# IMX7S_PMIC.net
KiCad netlist of a schematic drawn in Altium Designer
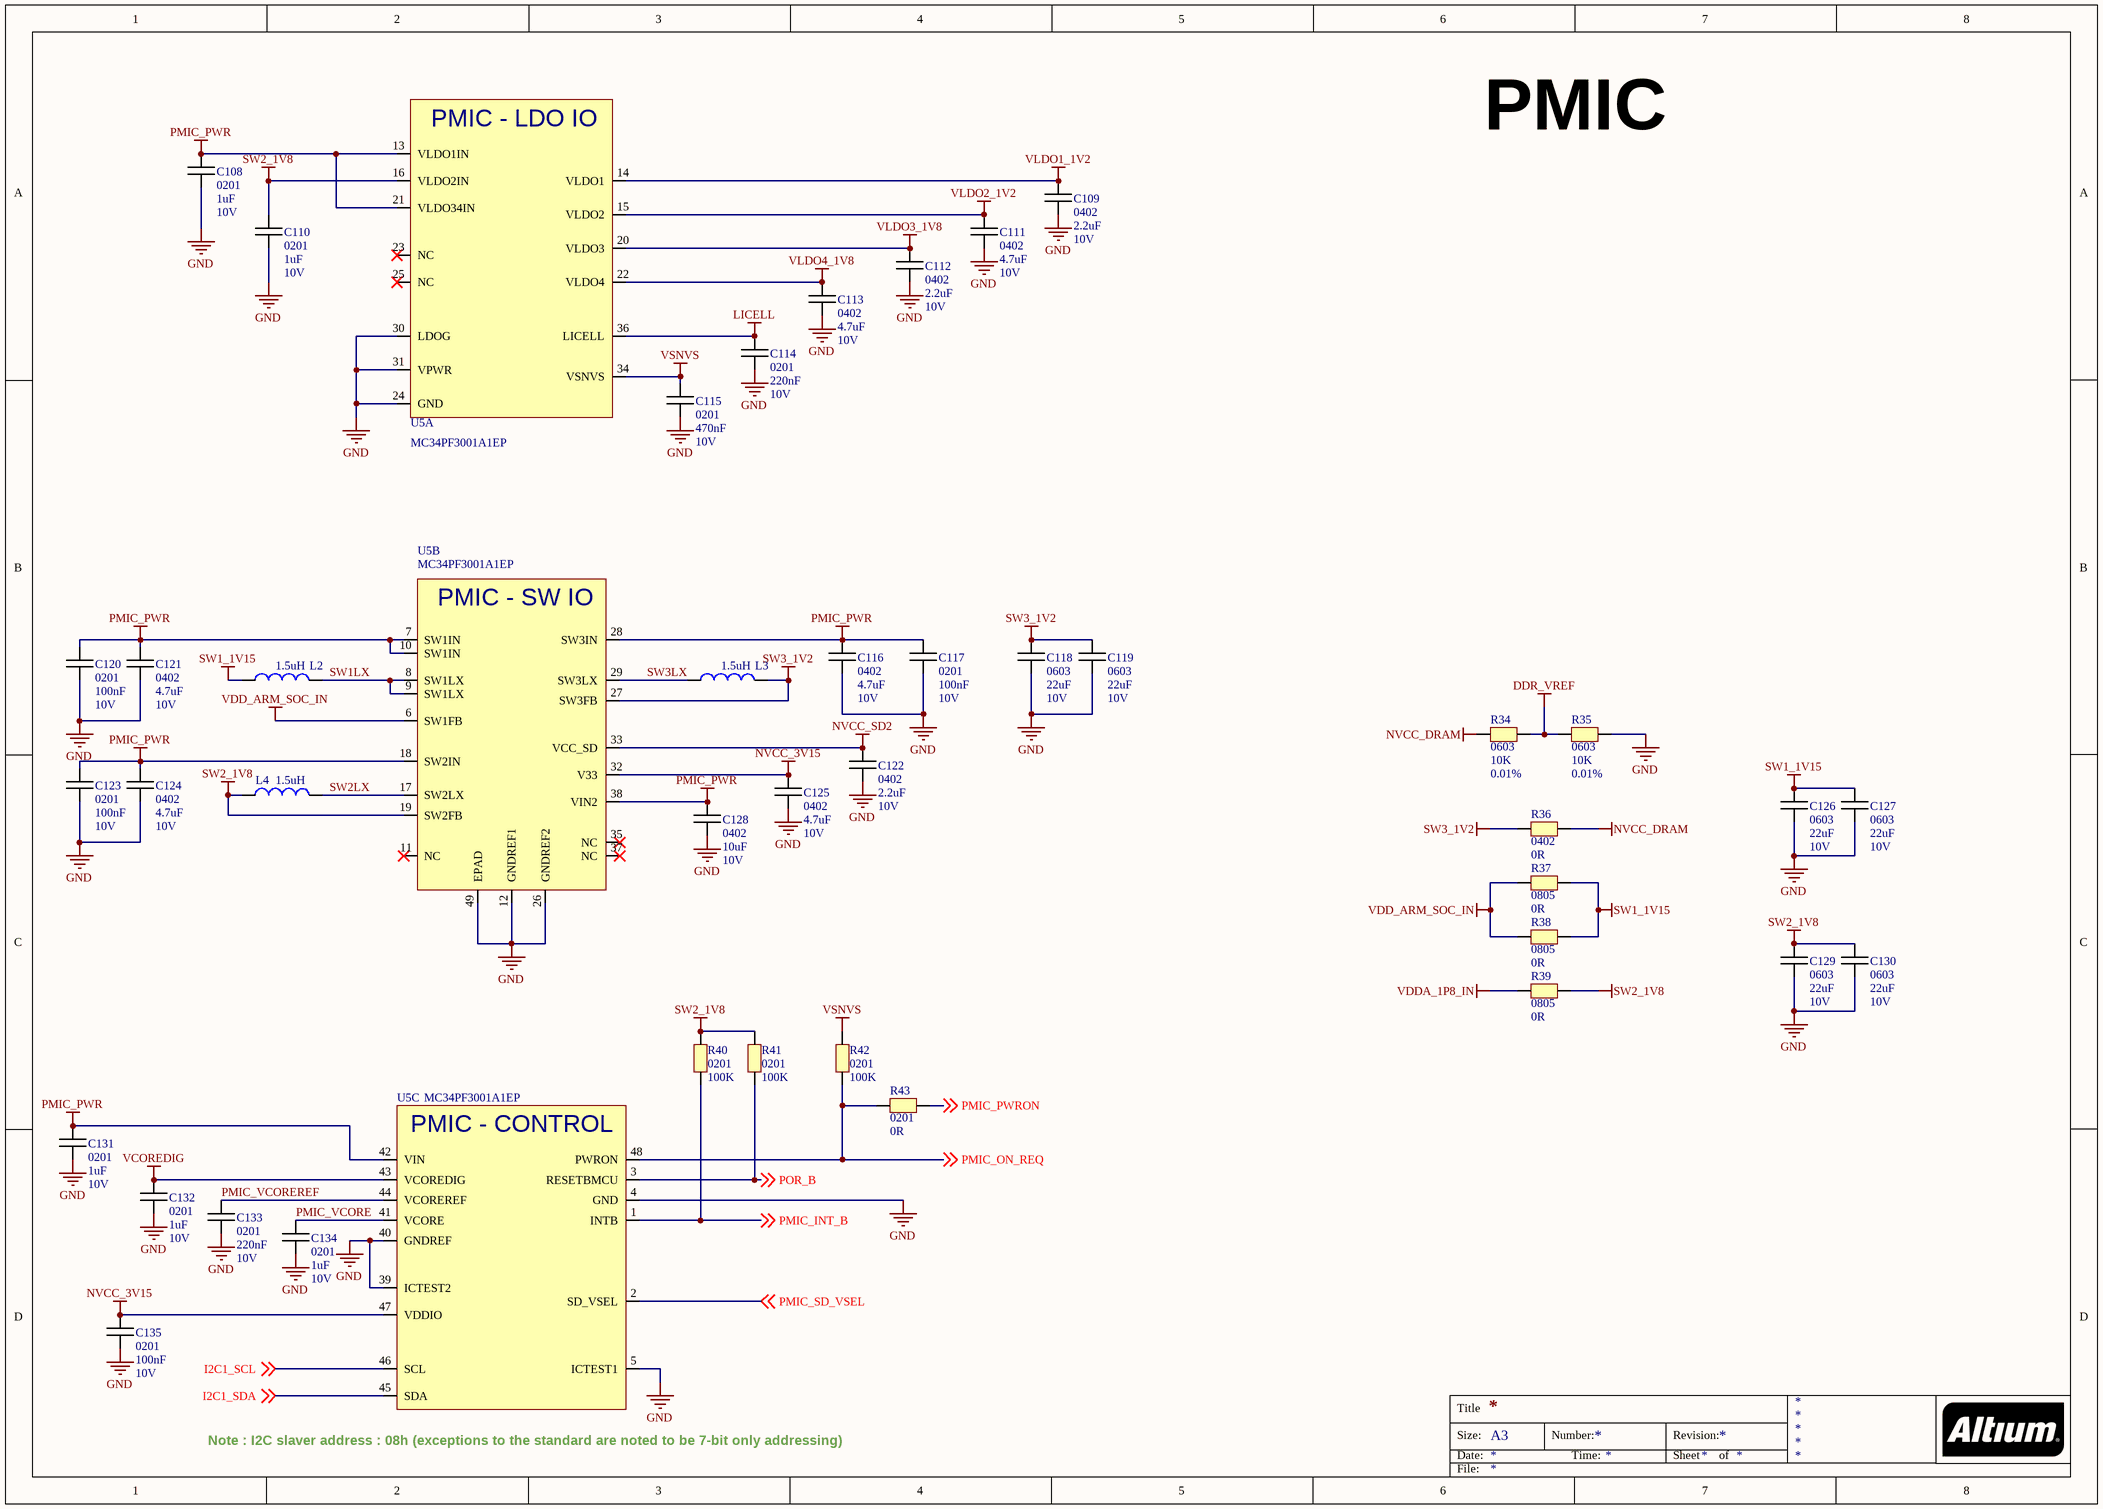
[diagram p0: IMX7S_PMIC.SchDoc]

(export (version "E")
  (design (tool "Eeschema 10.0.6"))
  (components
    (comp (ref "C108")
      (value "1uF")
      (footprint "C0201")
      (description "CAP CER 1UF 6.3V X5R 0201")
      (fields
        (field (name "PACKAGE") "0201")
        (field (name "VOLTAGE") "10V")
        (field (name "TOLERANCE") "20%")
        (field (name "Comment") "C0201")
      )
      (libsource (lib "Schlib_IMX7") (part "C0201"))
    )
    (comp (ref "C109")
      (value "2.2uF")
      (footprint "C0402")
      (fields
        (field (name "PACKAGE") "0402")
        (field (name "VOLTAGE") "10V")
        (field (name "TOLERANCE") "20%")
        (field (name "Comment") "C0402")
      )
      (libsource (lib "Schlib_IMX7") (part "C0402"))
    )
    (comp (ref "C110")
      (value "1uF")
      (footprint "C0201")
      (description "CAP CER 1UF 6.3V X5R 0201")
      (fields
        (field (name "PACKAGE") "0201")
        (field (name "VOLTAGE") "10V")
        (field (name "TOLERANCE") "20%")
        (field (name "Comment") "C0201")
      )
      (libsource (lib "Schlib_IMX7") (part "C0201"))
    )
    (comp (ref "C111")
      (value "4.7uF")
      (footprint "C0402")
      (fields (field (name "PACKAGE") "0402") (field (name "VOLTAGE") "10V") (field (name "Comment") "C0402"))
      (libsource (lib "Schlib_IMX7") (part "C0402"))
    )
    (comp (ref "C112")
      (value "2.2uF")
      (footprint "C0402")
      (fields
        (field (name "PACKAGE") "0402")
        (field (name "VOLTAGE") "10V")
        (field (name "TOLERANCE") "20%")
        (field (name "Comment") "C0402")
      )
      (libsource (lib "Schlib_IMX7") (part "C0402"))
    )
    (comp (ref "C113")
      (value "4.7uF")
      (footprint "C0402")
      (fields (field (name "PACKAGE") "0402") (field (name "VOLTAGE") "10V") (field (name "Comment") "C0402"))
      (libsource (lib "Schlib_IMX7") (part "C0402"))
    )
    (comp (ref "C114")
      (value "220nF")
      (footprint "C0201")
      (fields
        (field (name "PACKAGE") "0201")
        (field (name "VOLTAGE") "10V")
        (field (name "TOLERANCE") "10%")
        (field (name "Comment") "C0201")
      )
      (libsource (lib "Schlib_IMX7") (part "C0201"))
    )
    (comp (ref "C115")
      (value "470nF")
      (footprint "C0201")
      (fields (field (name "PACKAGE") "0201") (field (name "VOLTAGE") "10V") (field (name "Comment") "C0201"))
      (libsource (lib "Schlib_IMX7") (part "C0201"))
    )
    (comp (ref "C116")
      (value "4.7uF")
      (footprint "C0402")
      (fields (field (name "PACKAGE") "0402") (field (name "VOLTAGE") "10V") (field (name "Comment") "C0402"))
      (libsource (lib "Schlib_IMX7") (part "C0402"))
    )
    (comp (ref "C117")
      (value "100nF")
      (footprint "C0201")
      (fields
        (field (name "PACKAGE") "0201")
        (field (name "VOLTAGE") "10V")
        (field (name "TOLERANCE") "10%")
        (field (name "Comment") "C0201")
      )
      (libsource (lib "Schlib_IMX7") (part "C0201"))
    )
    (comp (ref "C118")
      (value "22uF")
      (footprint "C0603")
      (description "CAP, MLCC, X5R, 22UF, 10V, 0603")
      (fields
        (field (name "PACKAGE") "0603")
        (field (name "VOLTAGE") "10V")
        (field (name "TOLERANCE") "20%")
        (field (name "Comment") "C0603")
      )
      (libsource (lib "Schlib_IMX7") (part "C0603"))
    )
    (comp (ref "C119")
      (value "22uF")
      (footprint "C0603")
      (description "CAP, MLCC, X5R, 22UF, 10V, 0603")
      (fields
        (field (name "PACKAGE") "0603")
        (field (name "VOLTAGE") "10V")
        (field (name "TOLERANCE") "20%")
        (field (name "Comment") "C0603")
      )
      (libsource (lib "Schlib_IMX7") (part "C0603"))
    )
    (comp (ref "C120")
      (value "100nF")
      (footprint "C0201")
      (fields
        (field (name "PACKAGE") "0201")
        (field (name "VOLTAGE") "10V")
        (field (name "TOLERANCE") "10%")
        (field (name "Comment") "C0201")
      )
      (libsource (lib "Schlib_IMX7") (part "C0201"))
    )
    (comp (ref "C121")
      (value "4.7uF")
      (footprint "C0402")
      (fields (field (name "PACKAGE") "0402") (field (name "VOLTAGE") "10V") (field (name "Comment") "C0402"))
      (libsource (lib "Schlib_IMX7") (part "C0402"))
    )
    (comp (ref "C122")
      (value "2.2uF")
      (footprint "C0402")
      (fields
        (field (name "PACKAGE") "0402")
        (field (name "VOLTAGE") "10V")
        (field (name "TOLERANCE") "20%")
        (field (name "Comment") "C0402")
      )
      (libsource (lib "Schlib_IMX7") (part "C0402"))
    )
    (comp (ref "C123")
      (value "100nF")
      (footprint "C0201")
      (fields
        (field (name "PACKAGE") "0201")
        (field (name "VOLTAGE") "10V")
        (field (name "TOLERANCE") "10%")
        (field (name "Comment") "C0201")
      )
      (libsource (lib "Schlib_IMX7") (part "C0201"))
    )
    (comp (ref "C124")
      (value "4.7uF")
      (footprint "C0402")
      (fields (field (name "PACKAGE") "0402") (field (name "VOLTAGE") "10V") (field (name "Comment") "C0402"))
      (libsource (lib "Schlib_IMX7") (part "C0402"))
    )
    (comp (ref "C125")
      (value "4.7uF")
      (footprint "C0402")
      (fields (field (name "PACKAGE") "0402") (field (name "VOLTAGE") "10V") (field (name "Comment") "C0402"))
      (libsource (lib "Schlib_IMX7") (part "C0402"))
    )
    (comp (ref "C126")
      (value "22uF")
      (footprint "C0603")
      (description "CAP, MLCC, X5R, 22UF, 10V, 0603")
      (fields
        (field (name "PACKAGE") "0603")
        (field (name "VOLTAGE") "10V")
        (field (name "TOLERANCE") "20%")
        (field (name "Comment") "C0603")
      )
      (libsource (lib "Schlib_IMX7") (part "C0603"))
    )
    (comp (ref "C127")
      (value "22uF")
      (footprint "C0603")
      (description "CAP, MLCC, X5R, 22UF, 10V, 0603")
      (fields
        (field (name "PACKAGE") "0603")
        (field (name "VOLTAGE") "10V")
        (field (name "TOLERANCE") "20%")
        (field (name "Comment") "C0603")
      )
      (libsource (lib "Schlib_IMX7") (part "C0603"))
    )
    (comp (ref "C128")
      (value "10uF")
      (footprint "C0402")
      (fields
        (field (name "PACKAGE") "0402")
        (field (name "VOLTAGE") "10V")
        (field (name "TOLERANCE") "20%")
        (field (name "Comment") "C0402")
      )
      (libsource (lib "Schlib_IMX7") (part "C0402"))
    )
    (comp (ref "C129")
      (value "22uF")
      (footprint "C0603")
      (description "CAP, MLCC, X5R, 22UF, 10V, 0603")
      (fields
        (field (name "PACKAGE") "0603")
        (field (name "VOLTAGE") "10V")
        (field (name "TOLERANCE") "20%")
        (field (name "Comment") "C0603")
      )
      (libsource (lib "Schlib_IMX7") (part "C0603"))
    )
    (comp (ref "C130")
      (value "22uF")
      (footprint "C0603")
      (description "CAP, MLCC, X5R, 22UF, 10V, 0603")
      (fields
        (field (name "PACKAGE") "0603")
        (field (name "VOLTAGE") "10V")
        (field (name "TOLERANCE") "20%")
        (field (name "Comment") "C0603")
      )
      (libsource (lib "Schlib_IMX7") (part "C0603"))
    )
    (comp (ref "C131")
      (value "1uF")
      (footprint "C0201")
      (description "CAP CER 1UF 6.3V X5R 0201")
      (fields
        (field (name "PACKAGE") "0201")
        (field (name "VOLTAGE") "10V")
        (field (name "TOLERANCE") "20%")
        (field (name "Comment") "C0201")
      )
      (libsource (lib "Schlib_IMX7") (part "C0201"))
    )
    (comp (ref "C132")
      (value "1uF")
      (footprint "C0201")
      (description "CAP CER 1UF 6.3V X5R 0201")
      (fields
        (field (name "PACKAGE") "0201")
        (field (name "VOLTAGE") "10V")
        (field (name "TOLERANCE") "20%")
        (field (name "Comment") "C0201")
      )
      (libsource (lib "Schlib_IMX7") (part "C0201"))
    )
    (comp (ref "C133")
      (value "220nF")
      (footprint "C0201")
      (fields
        (field (name "PACKAGE") "0201")
        (field (name "VOLTAGE") "10V")
        (field (name "TOLERANCE") "10%")
        (field (name "Comment") "C0201")
      )
      (libsource (lib "Schlib_IMX7") (part "C0201"))
    )
    (comp (ref "C134")
      (value "1uF")
      (footprint "C0201")
      (description "CAP CER 1UF 6.3V X5R 0201")
      (fields
        (field (name "PACKAGE") "0201")
        (field (name "VOLTAGE") "10V")
        (field (name "TOLERANCE") "20%")
        (field (name "Comment") "C0201")
      )
      (libsource (lib "Schlib_IMX7") (part "C0201"))
    )
    (comp (ref "C135")
      (value "100nF")
      (footprint "C0201")
      (fields
        (field (name "PACKAGE") "0201")
        (field (name "VOLTAGE") "10V")
        (field (name "TOLERANCE") "10%")
        (field (name "Comment") "C0201")
      )
      (libsource (lib "Schlib_IMX7") (part "C0201"))
    )
    (comp (ref "L2")
      (value "1.5uH")
      (footprint "SELF")
      (fields (field (name "Comment") "Self"))
      (libsource (lib "Schlib_IMX7") (part "Self"))
    )
    (comp (ref "L3")
      (value "1.5uH")
      (footprint "SELF")
      (fields (field (name "Comment") "Self"))
      (libsource (lib "Schlib_IMX7") (part "Self"))
    )
    (comp (ref "L4")
      (value "1.5uH")
      (footprint "SELF")
      (fields (field (name "Comment") "Self"))
      (libsource (lib "Schlib_IMX7") (part "Self"))
    )
    (comp (ref "R34")
      (value "10K")
      (footprint "R0603")
      (description "GLOVE, NITROTOUGH, M, N230 - More Details")
      (fields
        (field (name "PACKAGE") "0603")
        (field (name "VOLTAGE") "0.01%")
        (field (name "TOLERANCE") "0.01%")
        (field (name "Comment") "R0603")
      )
      (libsource (lib "Schlib_IMX7") (part "R0603"))
    )
    (comp (ref "R35")
      (value "10K")
      (footprint "R0603")
      (description "GLOVE, NITROTOUGH, M, N230 - More Details")
      (fields
        (field (name "PACKAGE") "0603")
        (field (name "VOLTAGE") "0.01%")
        (field (name "TOLERANCE") "0.01%")
        (field (name "Comment") "R0603")
      )
      (libsource (lib "Schlib_IMX7") (part "R0603"))
    )
    (comp (ref "R36")
      (value "0R")
      (footprint "R0402")
      (description "MULTICOMP - MCSR04X000 PTL - RES, 0R0, 0.0625W, 0402, CERAMIC")
      (fields (field (name "PACKAGE") "0402") (field (name "VOLTAGE") "0V") (field (name "Comment") "R0402"))
      (libsource (lib "Schlib_IMX7") (part "R0402"))
    )
    (comp (ref "R37")
      (value "0R")
      (footprint "R0805")
      (description "MULTICOMP - MC01W08050R - RES, 0R0, 0.1W, , THICK FILM")
      (fields (field (name "PACKAGE") "0805") (field (name "VOLTAGE") "0V") (field (name "Comment") "R0805"))
      (libsource (lib "Schlib_IMX7") (part "R0805"))
    )
    (comp (ref "R38")
      (value "0R")
      (footprint "R0805")
      (description "MULTICOMP - MC01W08050R - RES, 0R0, 0.1W, , THICK FILM")
      (fields (field (name "PACKAGE") "0805") (field (name "VOLTAGE") "0V") (field (name "Comment") "R0805"))
      (libsource (lib "Schlib_IMX7") (part "R0805"))
    )
    (comp (ref "R39")
      (value "0R")
      (footprint "R0805")
      (description "MULTICOMP - MC01W08050R - RES, 0R0, 0.1W, , THICK FILM")
      (fields (field (name "PACKAGE") "0805") (field (name "VOLTAGE") "0V") (field (name "Comment") "R0805"))
      (libsource (lib "Schlib_IMX7") (part "R0805"))
    )
    (comp (ref "R40")
      (value "100K")
      (footprint "R0201")
      (description "MULTICOMP - MCWR02X1003FAL - RES, 100K, 1%, 0.05W, THICK FILM")
      (fields (field (name "PACKAGE") "0201") (field (name "VOLTAGE") "0V") (field (name "TOLERANCE") "1%"))
      (libsource (lib "Schlib_IMX7") (part "R0201"))
    )
    (comp (ref "R41")
      (value "100K")
      (footprint "R0201")
      (description "MULTICOMP - MCWR02X1003FAL - RES, 100K, 1%, 0.05W, THICK FILM")
      (fields (field (name "PACKAGE") "0201") (field (name "VOLTAGE") "0V") (field (name "TOLERANCE") "1%"))
      (libsource (lib "Schlib_IMX7") (part "R0201"))
    )
    (comp (ref "R42")
      (value "100K")
      (footprint "R0201")
      (description "MULTICOMP - MCWR02X1003FAL - RES, 100K, 1%, 0.05W, THICK FILM")
      (fields (field (name "PACKAGE") "0201") (field (name "VOLTAGE") "0V") (field (name "TOLERANCE") "1%"))
      (libsource (lib "Schlib_IMX7") (part "R0201"))
    )
    (comp (ref "R43")
      (value "0R")
      (footprint "R0201")
      (description "MULTICOMP - MCRE000086 - RES, 0R0, 1%, 0.05W, 0201, THICK FILM")
      (fields (field (name "PACKAGE") "0201") (field (name "VOLTAGE") "0V") (field (name "TOLERANCE") "1%"))
      (libsource (lib "") (part "R0201_1"))
    )
    (comp (ref "U5")
      (value "MC34PF3001A1EP")
      (footprint "QFN48")
      (libsource (lib "Schlib_IMX7") (part "MC34PF3001A1EP"))
    )
  )
  (nets
    (net (code "1") (name "/PMIC_VCORE") (class "Default")
      (node (ref "C134") (pin "2") (pinfunction "2_2") (pintype "passive"))
      (node (ref "U5") (pin "41") (pinfunction "VCORE_41") (pintype "passive"))
    )
    (net (code "2") (name "/PMIC_VCOREREF") (class "Default")
      (node (ref "C133") (pin "2") (pinfunction "2_2") (pintype "passive"))
      (node (ref "U5") (pin "44") (pinfunction "VCOREREF_44") (pintype "passive"))
    )
    (net (code "3") (name "/SW1LX") (class "Default")
      (node (ref "L2") (pin "2") (pintype "passive"))
      (node (ref "U5") (pin "8") (pinfunction "SW1LX_8") (pintype "passive"))
      (node (ref "U5") (pin "9") (pinfunction "SW1LX_9") (pintype "passive"))
    )
    (net (code "4") (name "/SW2LX") (class "Default")
      (node (ref "L4") (pin "2") (pintype "passive"))
      (node (ref "U5") (pin "17") (pinfunction "SW2LX_17") (pintype "passive"))
    )
    (net (code "5") (name "/SW3LX") (class "Default")
      (node (ref "L3") (pin "1") (pintype "passive"))
      (node (ref "U5") (pin "29") (pinfunction "SW3LX_29") (pintype "passive"))
    )
    (net (code "6") (name "DDR_VREF") (class "Default")
      (node (ref "R34") (pin "2") (pinfunction "2_2") (pintype "passive"))
      (node (ref "R35") (pin "1") (pinfunction "1_1") (pintype "passive"))
    )
    (net (code "7") (name "GND") (class "Default")
      (node (ref "C108") (pin "1") (pinfunction "1_1") (pintype "passive"))
      (node (ref "C109") (pin "1") (pinfunction "1_1") (pintype "passive"))
      (node (ref "C110") (pin "1") (pinfunction "1_1") (pintype "passive"))
      (node (ref "C111") (pin "1") (pinfunction "1_1") (pintype "passive"))
      (node (ref "C112") (pin "1") (pinfunction "1_1") (pintype "passive"))
      (node (ref "C113") (pin "1") (pinfunction "1_1") (pintype "passive"))
      (node (ref "C114") (pin "1") (pinfunction "1_1") (pintype "passive"))
      (node (ref "C115") (pin "1") (pinfunction "1_1") (pintype "passive"))
      (node (ref "C116") (pin "1") (pinfunction "1_1") (pintype "passive"))
      (node (ref "C117") (pin "1") (pinfunction "1_1") (pintype "passive"))
      (node (ref "C118") (pin "1") (pinfunction "1_1") (pintype "passive"))
      (node (ref "C119") (pin "1") (pinfunction "1_1") (pintype "passive"))
      (node (ref "C120") (pin "1") (pinfunction "1_1") (pintype "passive"))
      (node (ref "C121") (pin "1") (pinfunction "1_1") (pintype "passive"))
      (node (ref "C122") (pin "1") (pinfunction "1_1") (pintype "passive"))
      (node (ref "C123") (pin "1") (pinfunction "1_1") (pintype "passive"))
      (node (ref "C124") (pin "1") (pinfunction "1_1") (pintype "passive"))
      (node (ref "C125") (pin "1") (pinfunction "1_1") (pintype "passive"))
      (node (ref "C126") (pin "1") (pinfunction "1_1") (pintype "passive"))
      (node (ref "C127") (pin "1") (pinfunction "1_1") (pintype "passive"))
      (node (ref "C128") (pin "1") (pinfunction "1_1") (pintype "passive"))
      (node (ref "C129") (pin "1") (pinfunction "1_1") (pintype "passive"))
      (node (ref "C130") (pin "1") (pinfunction "1_1") (pintype "passive"))
      (node (ref "C131") (pin "1") (pinfunction "1_1") (pintype "passive"))
      (node (ref "C132") (pin "1") (pinfunction "1_1") (pintype "passive"))
      (node (ref "C133") (pin "1") (pinfunction "1_1") (pintype "passive"))
      (node (ref "C134") (pin "1") (pinfunction "1_1") (pintype "passive"))
      (node (ref "C135") (pin "1") (pinfunction "1_1") (pintype "passive"))
      (node (ref "R35") (pin "2") (pinfunction "2_2") (pintype "passive"))
      (node (ref "U5") (pin "12") (pinfunction "GNDREF1_12") (pintype "passive"))
      (node (ref "U5") (pin "24") (pinfunction "GND_24") (pintype "passive"))
      (node (ref "U5") (pin "26") (pinfunction "GNDREF2_26") (pintype "passive"))
      (node (ref "U5") (pin "30") (pinfunction "LDOG_30") (pintype "passive"))
      (node (ref "U5") (pin "31") (pinfunction "VPWR_31") (pintype "passive"))
      (node (ref "U5") (pin "39") (pinfunction "ICTEST2_39") (pintype "passive"))
      (node (ref "U5") (pin "4") (pinfunction "GND_4") (pintype "passive"))
      (node (ref "U5") (pin "40") (pinfunction "GNDREF_40") (pintype "passive"))
      (node (ref "U5") (pin "49") (pinfunction "EPAD_49") (pintype "passive"))
      (node (ref "U5") (pin "5") (pinfunction "ICTEST1_5") (pintype "passive"))
    )
    (net (code "8") (name "I2C1_SCL") (class "Default")
      (node (ref "U5") (pin "46") (pinfunction "SCL_46") (pintype "passive"))
    )
    (net (code "9") (name "I2C1_SDA") (class "Default")
      (node (ref "U5") (pin "45") (pinfunction "SDA_45") (pintype "passive"))
    )
    (net (code "10") (name "LICELL") (class "Default")
      (node (ref "C114") (pin "2") (pinfunction "2_2") (pintype "passive"))
      (node (ref "U5") (pin "36") (pinfunction "LICELL_36") (pintype "passive"))
    )
    (net (code "11") (name "NVCC_3V15") (class "Default")
      (node (ref "C125") (pin "2") (pinfunction "2_2") (pintype "passive"))
      (node (ref "C135") (pin "2") (pinfunction "2_2") (pintype "passive"))
      (node (ref "U5") (pin "32") (pinfunction "V33_32") (pintype "passive"))
      (node (ref "U5") (pin "47") (pinfunction "VDDIO_47") (pintype "passive"))
    )
    (net (code "12") (name "NVCC_DRAM") (class "Default")
      (node (ref "R34") (pin "1") (pinfunction "1_1") (pintype "passive"))
      (node (ref "R36") (pin "2") (pinfunction "2_2") (pintype "passive"))
    )
    (net (code "13") (name "NVCC_SD2") (class "Default")
      (node (ref "C122") (pin "2") (pinfunction "2_2") (pintype "passive"))
      (node (ref "U5") (pin "33") (pinfunction "VCC_SD_33") (pintype "passive"))
    )
    (net (code "14") (name "PMIC_INT_B") (class "Default")
      (node (ref "R40") (pin "1") (pinfunction "1_1") (pintype "passive"))
      (node (ref "U5") (pin "1") (pinfunction "INTB_1") (pintype "passive"))
    )
    (net (code "15") (name "PMIC_ON_REQ") (class "Default")
      (node (ref "R42") (pin "1") (pinfunction "1_1") (pintype "passive"))
      (node (ref "R43") (pin "2") (pinfunction "2_2") (pintype "passive"))
      (node (ref "U5") (pin "48") (pinfunction "PWRON_48") (pintype "passive"))
    )
    (net (code "16") (name "PMIC_PWR") (class "Default")
      (node (ref "C108") (pin "2") (pinfunction "2_2") (pintype "passive"))
      (node (ref "C116") (pin "2") (pinfunction "2_2") (pintype "passive"))
      (node (ref "C117") (pin "2") (pinfunction "2_2") (pintype "passive"))
      (node (ref "C120") (pin "2") (pinfunction "2_2") (pintype "passive"))
      (node (ref "C121") (pin "2") (pinfunction "2_2") (pintype "passive"))
      (node (ref "C123") (pin "2") (pinfunction "2_2") (pintype "passive"))
      (node (ref "C124") (pin "2") (pinfunction "2_2") (pintype "passive"))
      (node (ref "C128") (pin "2") (pinfunction "2_2") (pintype "passive"))
      (node (ref "C131") (pin "2") (pinfunction "2_2") (pintype "passive"))
      (node (ref "U5") (pin "10") (pinfunction "SW1IN_10") (pintype "passive"))
      (node (ref "U5") (pin "13") (pinfunction "VLDO1IN_13") (pintype "passive"))
      (node (ref "U5") (pin "18") (pinfunction "SW2IN_18") (pintype "passive"))
      (node (ref "U5") (pin "21") (pinfunction "VLDO34IN_21") (pintype "passive"))
      (node (ref "U5") (pin "28") (pinfunction "SW3IN_28") (pintype "passive"))
      (node (ref "U5") (pin "38") (pinfunction "VIN2_38") (pintype "passive"))
      (node (ref "U5") (pin "42") (pinfunction "VIN_42") (pintype "passive"))
      (node (ref "U5") (pin "7") (pinfunction "SW1IN_7") (pintype "passive"))
    )
    (net (code "17") (name "PMIC_PWRON") (class "Default")
      (node (ref "R43") (pin "1") (pinfunction "1_1") (pintype "passive"))
    )
    (net (code "18") (name "PMIC_SD_VSEL") (class "Default")
      (node (ref "U5") (pin "2") (pinfunction "SD_VSEL_2") (pintype "passive"))
    )
    (net (code "19") (name "POR_B") (class "Default")
      (node (ref "R41") (pin "1") (pinfunction "1_1") (pintype "passive"))
      (node (ref "U5") (pin "3") (pinfunction "RESETBMCU_3") (pintype "passive"))
    )
    (net (code "20") (name "SW1_1V15") (class "Default")
      (node (ref "C126") (pin "2") (pinfunction "2_2") (pintype "passive"))
      (node (ref "C127") (pin "2") (pinfunction "2_2") (pintype "passive"))
      (node (ref "L2") (pin "1") (pintype "passive"))
      (node (ref "R37") (pin "2") (pinfunction "2_2") (pintype "passive"))
      (node (ref "R38") (pin "2") (pinfunction "2_2") (pintype "passive"))
    )
    (net (code "21") (name "SW2_1V8") (class "Default")
      (node (ref "C110") (pin "2") (pinfunction "2_2") (pintype "passive"))
      (node (ref "C129") (pin "2") (pinfunction "2_2") (pintype "passive"))
      (node (ref "C130") (pin "2") (pinfunction "2_2") (pintype "passive"))
      (node (ref "L4") (pin "1") (pintype "passive"))
      (node (ref "R39") (pin "2") (pinfunction "2_2") (pintype "passive"))
      (node (ref "R40") (pin "2") (pinfunction "2_2") (pintype "passive"))
      (node (ref "R41") (pin "2") (pinfunction "2_2") (pintype "passive"))
      (node (ref "U5") (pin "16") (pinfunction "VLDO2IN_16") (pintype "passive"))
      (node (ref "U5") (pin "19") (pinfunction "SW2FB_19") (pintype "passive"))
    )
    (net (code "22") (name "SW3_1V2") (class "Default")
      (node (ref "C118") (pin "2") (pinfunction "2_2") (pintype "passive"))
      (node (ref "C119") (pin "2") (pinfunction "2_2") (pintype "passive"))
      (node (ref "L3") (pin "2") (pintype "passive"))
      (node (ref "R36") (pin "1") (pinfunction "1_1") (pintype "passive"))
      (node (ref "U5") (pin "27") (pinfunction "SW3FB_27") (pintype "passive"))
    )
    (net (code "23") (name "VCOREDIG") (class "Default")
      (node (ref "C132") (pin "2") (pinfunction "2_2") (pintype "passive"))
      (node (ref "U5") (pin "43") (pinfunction "VCOREDIG_43") (pintype "passive"))
    )
    (net (code "24") (name "VDDA_1P8_IN") (class "Default")
      (node (ref "R39") (pin "1") (pinfunction "1_1") (pintype "passive"))
    )
    (net (code "25") (name "VDD_ARM_SOC_IN") (class "Default")
      (node (ref "R37") (pin "1") (pinfunction "1_1") (pintype "passive"))
      (node (ref "R38") (pin "1") (pinfunction "1_1") (pintype "passive"))
      (node (ref "U5") (pin "6") (pinfunction "SW1FB_6") (pintype "passive"))
    )
    (net (code "26") (name "VLDO1_1V2") (class "Default")
      (node (ref "C109") (pin "2") (pinfunction "2_2") (pintype "passive"))
      (node (ref "U5") (pin "14") (pinfunction "VLDO1_14") (pintype "passive"))
    )
    (net (code "27") (name "VLDO2_1V2") (class "Default")
      (node (ref "C111") (pin "2") (pinfunction "2_2") (pintype "passive"))
      (node (ref "U5") (pin "15") (pinfunction "VLDO2_15") (pintype "passive"))
    )
    (net (code "28") (name "VLDO3_1V8") (class "Default")
      (node (ref "C112") (pin "2") (pinfunction "2_2") (pintype "passive"))
      (node (ref "U5") (pin "20") (pinfunction "VLDO3_20") (pintype "passive"))
    )
    (net (code "29") (name "VLDO4_1V8") (class "Default")
      (node (ref "C113") (pin "2") (pinfunction "2_2") (pintype "passive"))
      (node (ref "U5") (pin "22") (pinfunction "VLDO4_22") (pintype "passive"))
    )
    (net (code "30") (name "VSNVS") (class "Default")
      (node (ref "C115") (pin "2") (pinfunction "2_2") (pintype "passive"))
      (node (ref "R42") (pin "2") (pinfunction "2_2") (pintype "passive"))
      (node (ref "U5") (pin "34") (pinfunction "VSNVS_34") (pintype "passive"))
    )
    (net (code "31") (name "unconnected-(U5A-NC-Pad23)") (class "Default")
      (node (ref "U5") (pin "23") (pinfunction "NC_23") (pintype "passive+no_connect"))
    )
    (net (code "32") (name "unconnected-(U5A-NC-Pad25)") (class "Default")
      (node (ref "U5") (pin "25") (pinfunction "NC_25") (pintype "passive+no_connect"))
    )
    (net (code "33") (name "unconnected-(U5B-NC-Pad11)") (class "Default")
      (node (ref "U5") (pin "11") (pinfunction "NC_11") (pintype "passive+no_connect"))
    )
    (net (code "34") (name "unconnected-(U5B-NC-Pad35)") (class "Default")
      (node (ref "U5") (pin "35") (pinfunction "NC_35") (pintype "passive+no_connect"))
    )
    (net (code "35") (name "unconnected-(U5B-NC-Pad37)") (class "Default")
      (node (ref "U5") (pin "37") (pinfunction "NC_37") (pintype "passive+no_connect"))
    )
  )
)
